# ESP-Breakout_Bd.net
KiCad netlist of a schematic drawn in EAGLE
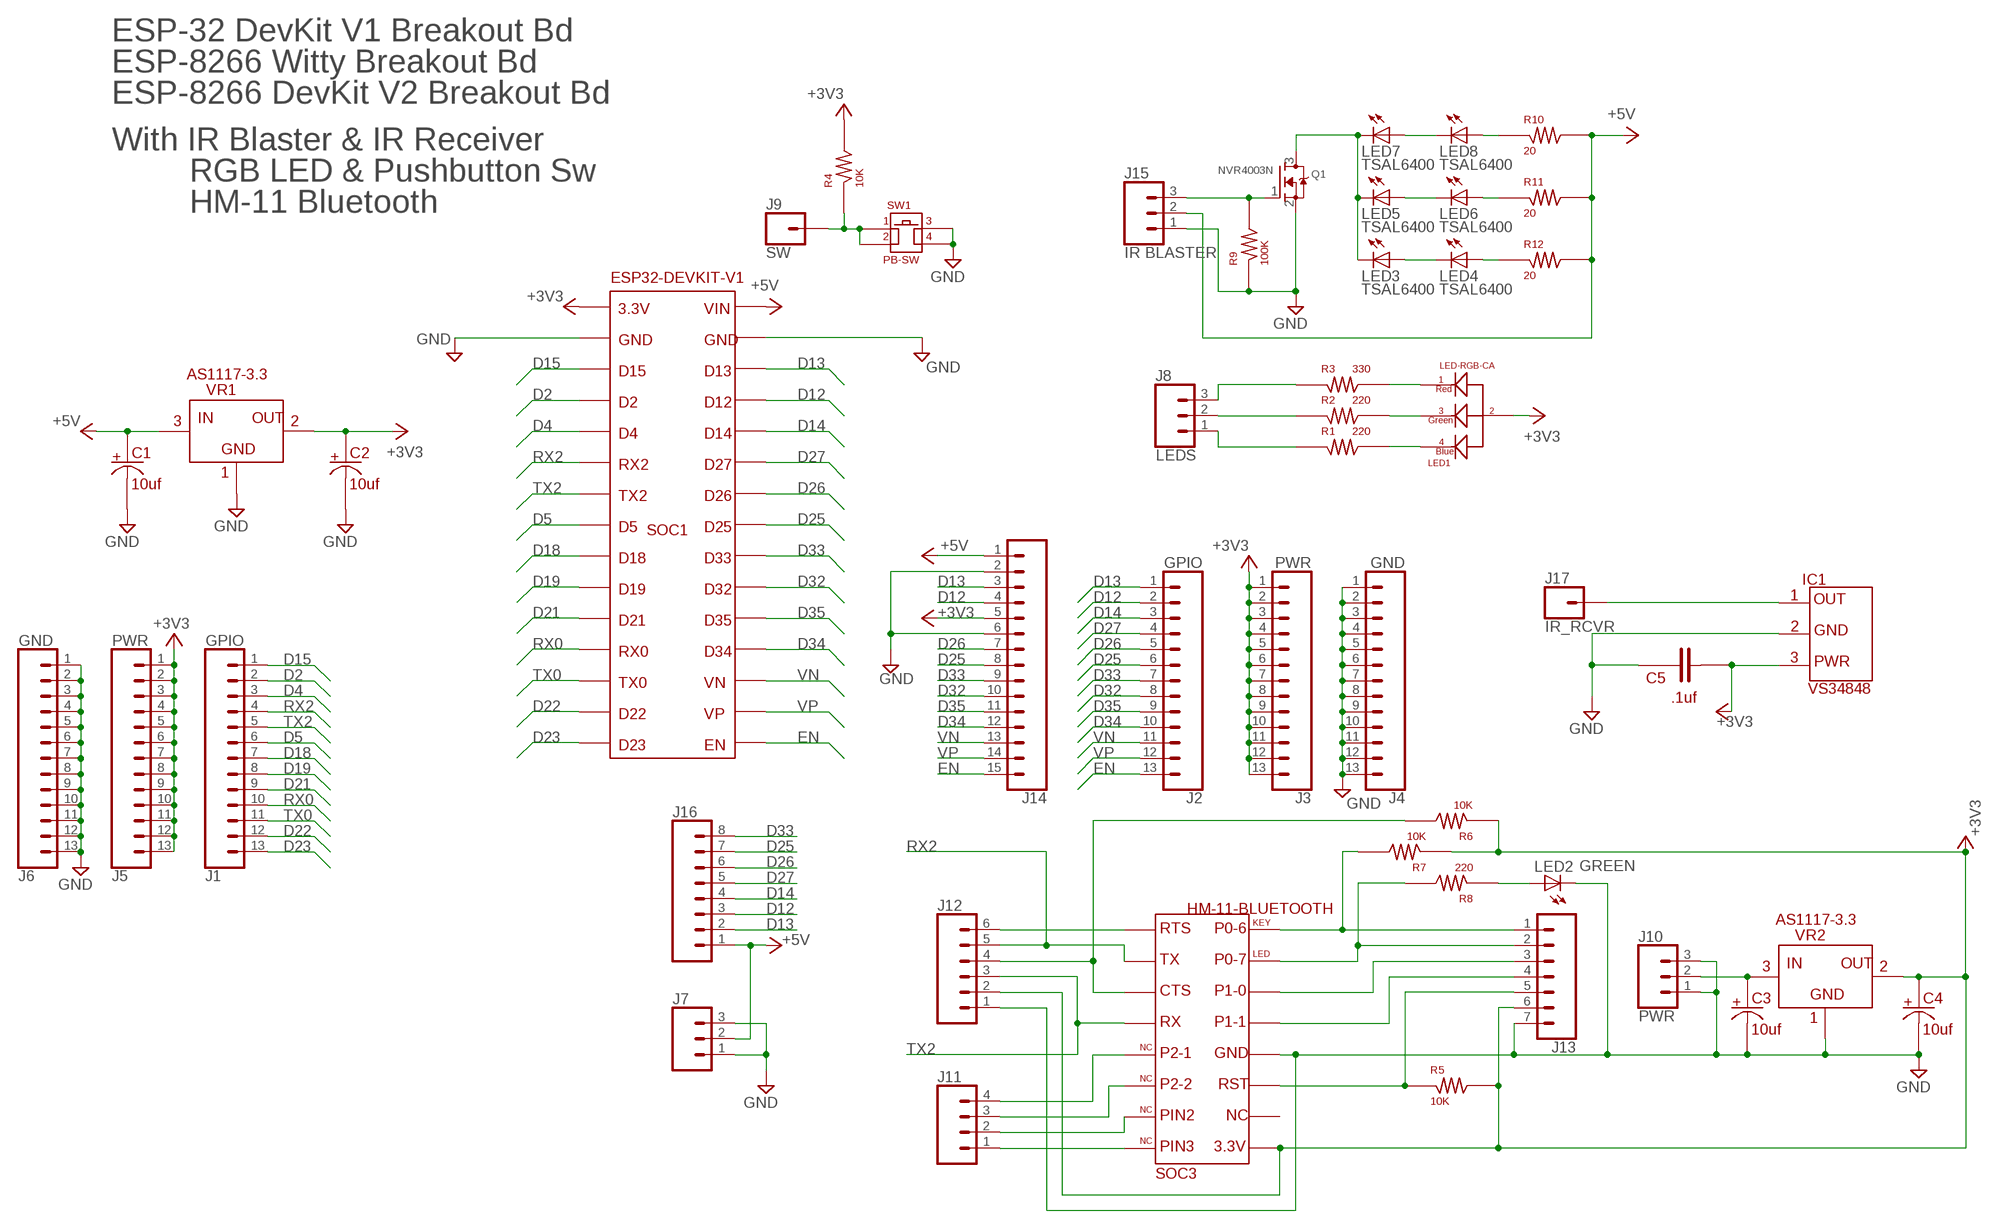
[diagram p0: schematic, sheet 1]

(export (version "E")
  (design (tool "Eeschema 10.0.6"))
  (components
    (comp (ref "C1")
      (value "10uf")
      (footprint "eagle-import:SMT-B")
      (libsource (lib "eagle-import") (part "CAP-POL-SMT-B"))
    )
    (comp (ref "C2")
      (value "10uf")
      (footprint "eagle-import:SMT-B")
      (libsource (lib "eagle-import") (part "CAP-POL-SMT-B"))
    )
    (comp (ref "C3")
      (value "10uf")
      (footprint "eagle-import:SMT-B")
      (libsource (lib "eagle-import") (part "CAP-POL-SMT-B"))
    )
    (comp (ref "C4")
      (value "10uf")
      (footprint "eagle-import:SMT-B")
      (libsource (lib "eagle-import") (part "CAP-POL-SMT-B"))
    )
    (comp (ref "C5")
      (value ".1uf")
      (footprint "eagle-import:CAP-2.5MM-ROUND")
      (libsource (lib "eagle-import") (part "NPCAP-2.5MM-ROUND"))
    )
    (comp (ref "IC1")
      (value "VS34848")
      (footprint "eagle-import:VS34838")
      (libsource (lib "eagle-import") (part "VS34848"))
    )
    (comp (ref "J1")
      (value "GPIO")
      (footprint "eagle-import:1X13")
      (libsource (lib "eagle-import") (part "CONN_13"))
    )
    (comp (ref "J2")
      (value "GPIO")
      (footprint "eagle-import:1X13")
      (libsource (lib "eagle-import") (part "CONN_13"))
    )
    (comp (ref "J3")
      (value "PWR")
      (footprint "eagle-import:1X13")
      (libsource (lib "eagle-import") (part "CONN_13"))
    )
    (comp (ref "J4")
      (value "GND")
      (footprint "eagle-import:1X13")
      (libsource (lib "eagle-import") (part "CONN_13"))
    )
    (comp (ref "J5")
      (value "PWR")
      (footprint "eagle-import:1X13")
      (libsource (lib "eagle-import") (part "CONN_13"))
    )
    (comp (ref "J6")
      (value "GND")
      (footprint "eagle-import:1X13")
      (libsource (lib "eagle-import") (part "CONN_13"))
    )
    (comp (ref "J7")
      (value "CONN_03")
      (footprint "eagle-import:1X03")
      (libsource (lib "eagle-import") (part "CONN_03"))
    )
    (comp (ref "J8")
      (value "LEDS")
      (footprint "eagle-import:1X03")
      (libsource (lib "eagle-import") (part "CONN_03"))
    )
    (comp (ref "J9")
      (value "SW")
      (footprint "eagle-import:1X01")
      (libsource (lib "eagle-import") (part "CONN_01"))
    )
    (comp (ref "J10")
      (value "PWR")
      (footprint "eagle-import:1X03")
      (libsource (lib "eagle-import") (part "CONN_03"))
    )
    (comp (ref "J11")
      (value "CONN_04")
      (footprint "eagle-import:1X04")
      (libsource (lib "eagle-import") (part "CONN_04"))
    )
    (comp (ref "J12")
      (value "CONN_06SILK_FEMALE_PTH")
      (footprint "eagle-import:1X06")
      (libsource (lib "eagle-import") (part "CONN_06SILK_FEMALE_PTH"))
    )
    (comp (ref "J13")
      (value "CONN_07")
      (footprint "eagle-import:1X07")
      (libsource (lib "eagle-import") (part "CONN_07"))
    )
    (comp (ref "J14")
      (value "CONN_15")
      (footprint "eagle-import:1X15")
      (libsource (lib "eagle-import") (part "CONN_15"))
    )
    (comp (ref "J15")
      (value "IR BLASTER")
      (footprint "eagle-import:1X03")
      (libsource (lib "eagle-import") (part "CONN_03"))
    )
    (comp (ref "J16")
      (value "CONN_08\"")
      (footprint "eagle-import:1X08")
      (libsource (lib "eagle-import") (part "CONN_08{dblquote}"))
    )
    (comp (ref "J17")
      (value "IR_RCVR")
      (footprint "eagle-import:1X01")
      (libsource (lib "eagle-import") (part "CONN_01"))
    )
    (comp (ref "LED1")
      (value "LED-RGB-CA")
      (footprint "eagle-import:LED-RGB-5MM")
      (libsource (lib "eagle-import") (part "LED-RGB-CA"))
    )
    (comp (ref "LED2")
      (value "GREEN")
      (footprint "eagle-import:CHIPLED_0805")
      (libsource (lib "eagle-import") (part "LEDCHIPLED_0805"))
    )
    (comp (ref "LED3")
      (value "TSAL6400")
      (footprint "eagle-import:LED5MM")
      (libsource (lib "eagle-import") (part "LED5MM"))
    )
    (comp (ref "LED4")
      (value "TSAL6400")
      (footprint "eagle-import:LED5MM")
      (libsource (lib "eagle-import") (part "LED5MM"))
    )
    (comp (ref "LED5")
      (value "TSAL6400")
      (footprint "eagle-import:LED5MM")
      (libsource (lib "eagle-import") (part "LED5MM"))
    )
    (comp (ref "LED6")
      (value "TSAL6400")
      (footprint "eagle-import:LED5MM")
      (libsource (lib "eagle-import") (part "LED5MM"))
    )
    (comp (ref "LED7")
      (value "TSAL6400")
      (footprint "eagle-import:LED5MM")
      (libsource (lib "eagle-import") (part "LED5MM"))
    )
    (comp (ref "LED8")
      (value "TSAL6400")
      (footprint "eagle-import:LED5MM")
      (libsource (lib "eagle-import") (part "LED5MM"))
    )
    (comp (ref "Q1")
      (value "NVR4003N")
      (footprint "eagle-import:SOT23")
      (libsource (lib "eagle-import") (part "MOSFET-NREFLOW"))
    )
    (comp (ref "R1")
      (value "220")
      (footprint "eagle-import:SMT-1206-TOP")
      (libsource (lib "eagle-import") (part "RESISTOR-1206-TOP"))
    )
    (comp (ref "R2")
      (value "220")
      (footprint "eagle-import:SMT-1206-TOP")
      (libsource (lib "eagle-import") (part "RESISTOR-1206-TOP"))
    )
    (comp (ref "R3")
      (value "330")
      (footprint "eagle-import:SMT-1206-TOP")
      (libsource (lib "eagle-import") (part "RESISTOR-1206-TOP"))
    )
    (comp (ref "R4")
      (value "10K")
      (footprint "eagle-import:SMT-1206-TOP")
      (libsource (lib "eagle-import") (part "RESISTOR-1206-TOP"))
    )
    (comp (ref "R5")
      (value "10K")
      (footprint "eagle-import:SMT-0603")
      (libsource (lib "eagle-import") (part "RESISTOR-SMT-0603"))
    )
    (comp (ref "R6")
      (value "10K")
      (footprint "eagle-import:SMT-0603")
      (libsource (lib "eagle-import") (part "RESISTOR-SMT-0603"))
    )
    (comp (ref "R7")
      (value "10K")
      (footprint "eagle-import:SMT-0603")
      (libsource (lib "eagle-import") (part "RESISTOR-SMT-0603"))
    )
    (comp (ref "R8")
      (value "220")
      (footprint "eagle-import:SMT-0603")
      (libsource (lib "eagle-import") (part "RESISTOR-SMT-0603"))
    )
    (comp (ref "R9")
      (value "100K")
      (footprint "eagle-import:SMT-0603")
      (libsource (lib "eagle-import") (part "RESISTOR-SMT-0603"))
    )
    (comp (ref "R10")
      (value "20")
      (footprint "eagle-import:1_2WATT")
      (libsource (lib "eagle-import") (part "1/2WATT"))
    )
    (comp (ref "R11")
      (value "20")
      (footprint "eagle-import:1_2WATT")
      (libsource (lib "eagle-import") (part "1/2WATT"))
    )
    (comp (ref "R12")
      (value "20")
      (footprint "eagle-import:1_2WATT")
      (libsource (lib "eagle-import") (part "1/2WATT"))
    )
    (comp (ref "SOC1")
      (value "ESP32-DEVKIT-V1")
      (footprint "eagle-import:ESP32-DEVKIT-V1")
      (libsource (lib "eagle-import") (part "ESP32-DEVKIT-V1"))
    )
    (comp (ref "SOC3")
      (value "HM-11-BLUETOOTH")
      (footprint "eagle-import:HM-11")
      (libsource (lib "eagle-import") (part "HM-11-BLUETOOTH"))
    )
    (comp (ref "SW1")
      (value "PB-SW")
      (footprint "eagle-import:PB-SW")
      (libsource (lib "eagle-import") (part "PB-SW"))
    )
    (comp (ref "VR1")
      (value "AS1117-3.3")
      (footprint "eagle-import:SOT-223")
      (libsource (lib "eagle-import") (part "AS1117"))
    )
    (comp (ref "VR2")
      (value "AS1117-3.3")
      (footprint "eagle-import:SOT-223")
      (libsource (lib "eagle-import") (part "AS1117"))
    )
  )
  (nets
    (net (code "1") (name "+3V3") (class "Default")
      (node (ref "C2") (pin "P$1") (pinfunction "P$1_P$1") (pintype "passive"))
      (node (ref "C4") (pin "P$1") (pinfunction "P$1_P$1") (pintype "passive"))
      (node (ref "C5") (pin "P$2") (pinfunction "2_P$2") (pintype "passive"))
      (node (ref "IC1") (pin "P$3") (pinfunction "P$3_P$3") (pintype "bidirectional"))
      (node (ref "J12") (pin "2") (pinfunction "2_2") (pintype "passive"))
      (node (ref "J13") (pin "6") (pinfunction "6_6") (pintype "passive"))
      (node (ref "J14") (pin "5") (pinfunction "5_5") (pintype "passive"))
      (node (ref "J3") (pin "1") (pinfunction "1_1") (pintype "passive"))
      (node (ref "J3") (pin "10") (pinfunction "10_10") (pintype "passive"))
      (node (ref "J3") (pin "11") (pinfunction "11_11") (pintype "passive"))
      (node (ref "J3") (pin "12") (pinfunction "12_12") (pintype "passive"))
      (node (ref "J3") (pin "13") (pinfunction "13_13") (pintype "passive"))
      (node (ref "J3") (pin "2") (pinfunction "2_2") (pintype "passive"))
      (node (ref "J3") (pin "3") (pinfunction "3_3") (pintype "passive"))
      (node (ref "J3") (pin "4") (pinfunction "4_4") (pintype "passive"))
      (node (ref "J3") (pin "5") (pinfunction "5_5") (pintype "passive"))
      (node (ref "J3") (pin "6") (pinfunction "6_6") (pintype "passive"))
      (node (ref "J3") (pin "7") (pinfunction "7_7") (pintype "passive"))
      (node (ref "J3") (pin "8") (pinfunction "8_8") (pintype "passive"))
      (node (ref "J3") (pin "9") (pinfunction "9_9") (pintype "passive"))
      (node (ref "J5") (pin "1") (pinfunction "1_1") (pintype "passive"))
      (node (ref "J5") (pin "10") (pinfunction "10_10") (pintype "passive"))
      (node (ref "J5") (pin "11") (pinfunction "11_11") (pintype "passive"))
      (node (ref "J5") (pin "12") (pinfunction "12_12") (pintype "passive"))
      (node (ref "J5") (pin "13") (pinfunction "13_13") (pintype "passive"))
      (node (ref "J5") (pin "2") (pinfunction "2_2") (pintype "passive"))
      (node (ref "J5") (pin "3") (pinfunction "3_3") (pintype "passive"))
      (node (ref "J5") (pin "4") (pinfunction "4_4") (pintype "passive"))
      (node (ref "J5") (pin "5") (pinfunction "5_5") (pintype "passive"))
      (node (ref "J5") (pin "6") (pinfunction "6_6") (pintype "passive"))
      (node (ref "J5") (pin "7") (pinfunction "7_7") (pintype "passive"))
      (node (ref "J5") (pin "8") (pinfunction "8_8") (pintype "passive"))
      (node (ref "J5") (pin "9") (pinfunction "9_9") (pintype "passive"))
      (node (ref "LED1") (pin "P$2") (pinfunction "P$2_P$2") (pintype "bidirectional"))
      (node (ref "R4") (pin "P$2") (pinfunction "P$2_P$2") (pintype "bidirectional"))
      (node (ref "R5") (pin "P$2") (pinfunction "P$2_P$2") (pintype "bidirectional"))
      (node (ref "R6") (pin "P$1") (pinfunction "P$1_P$1") (pintype "bidirectional"))
      (node (ref "R7") (pin "P$1") (pinfunction "P$1_P$1") (pintype "bidirectional"))
      (node (ref "SOC1") (pin "P$1") (pinfunction "P$1_P$1") (pintype "bidirectional"))
      (node (ref "SOC3") (pin "P$9") (pinfunction "P$9_P$9") (pintype "bidirectional"))
      (node (ref "VR1") (pin "P$2") (pinfunction "P$2_P$2") (pintype "bidirectional"))
      (node (ref "VR1") (pin "P$4") (pinfunction "P$2_P$4") (pintype "bidirectional"))
      (node (ref "VR2") (pin "P$2") (pinfunction "P$2_P$2") (pintype "bidirectional"))
      (node (ref "VR2") (pin "P$4") (pinfunction "P$2_P$4") (pintype "bidirectional"))
    )
    (net (code "2") (name "+5V") (class "Default")
      (node (ref "C1") (pin "P$1") (pinfunction "P$1_P$1") (pintype "passive"))
      (node (ref "J14") (pin "1") (pinfunction "1_1") (pintype "passive"))
      (node (ref "J15") (pin "2") (pinfunction "2_2") (pintype "passive"))
      (node (ref "J16") (pin "1") (pinfunction "1_1") (pintype "passive"))
      (node (ref "J7") (pin "2") (pinfunction "2_2") (pintype "passive"))
      (node (ref "R10") (pin "P$2") (pinfunction "P$2_P$2") (pintype "bidirectional"))
      (node (ref "R11") (pin "P$2") (pinfunction "P$2_P$2") (pintype "bidirectional"))
      (node (ref "R12") (pin "P$2") (pinfunction "P$2_P$2") (pintype "bidirectional"))
      (node (ref "SOC1") (pin "P$30") (pinfunction "P$30_P$30") (pintype "bidirectional"))
      (node (ref "VR1") (pin "P$3") (pinfunction "P$3_P$3") (pintype "bidirectional"))
    )
    (net (code "3") (name "/D2") (class "Default")
      (node (ref "J1") (pin "2") (pinfunction "2_2") (pintype "passive"))
      (node (ref "SOC1") (pin "P$4") (pinfunction "P$4_P$4") (pintype "bidirectional"))
    )
    (net (code "4") (name "/D4") (class "Default")
      (node (ref "J1") (pin "3") (pinfunction "3_3") (pintype "passive"))
      (node (ref "SOC1") (pin "P$5") (pinfunction "P$5_P$5") (pintype "bidirectional"))
    )
    (net (code "5") (name "/D5") (class "Default")
      (node (ref "J1") (pin "6") (pinfunction "6_6") (pintype "passive"))
      (node (ref "SOC1") (pin "P$8") (pinfunction "P$8_P$8") (pintype "bidirectional"))
    )
    (net (code "6") (name "/D12") (class "Default")
      (node (ref "J14") (pin "4") (pinfunction "4_4") (pintype "passive"))
      (node (ref "J16") (pin "3") (pinfunction "3_3") (pintype "passive"))
      (node (ref "J2") (pin "2") (pinfunction "2_2") (pintype "passive"))
      (node (ref "SOC1") (pin "P$27") (pinfunction "P$27_P$27") (pintype "bidirectional"))
    )
    (net (code "7") (name "/D13") (class "Default")
      (node (ref "J14") (pin "3") (pinfunction "3_3") (pintype "passive"))
      (node (ref "J16") (pin "2") (pinfunction "2_2") (pintype "passive"))
      (node (ref "J2") (pin "1") (pinfunction "1_1") (pintype "passive"))
      (node (ref "SOC1") (pin "P$28") (pinfunction "P$28_P$28") (pintype "bidirectional"))
    )
    (net (code "8") (name "/D14") (class "Default")
      (node (ref "J16") (pin "4") (pinfunction "4_4") (pintype "passive"))
      (node (ref "J2") (pin "3") (pinfunction "3_3") (pintype "passive"))
      (node (ref "SOC1") (pin "P$26") (pinfunction "P$26_P$26") (pintype "bidirectional"))
    )
    (net (code "9") (name "/D15") (class "Default")
      (node (ref "J1") (pin "1") (pinfunction "1_1") (pintype "passive"))
      (node (ref "SOC1") (pin "P$3") (pinfunction "P$3_P$3") (pintype "bidirectional"))
    )
    (net (code "10") (name "/D18") (class "Default")
      (node (ref "J1") (pin "7") (pinfunction "7_7") (pintype "passive"))
      (node (ref "SOC1") (pin "P$9") (pinfunction "P$9_P$9") (pintype "bidirectional"))
    )
    (net (code "11") (name "/D19") (class "Default")
      (node (ref "J1") (pin "8") (pinfunction "8_8") (pintype "passive"))
      (node (ref "SOC1") (pin "P$10") (pinfunction "P$10_P$10") (pintype "bidirectional"))
    )
    (net (code "12") (name "/D21") (class "Default")
      (node (ref "J1") (pin "9") (pinfunction "9_9") (pintype "passive"))
      (node (ref "SOC1") (pin "P$11") (pinfunction "P$11_P$11") (pintype "bidirectional"))
    )
    (net (code "13") (name "/D22") (class "Default")
      (node (ref "J1") (pin "12") (pinfunction "12_12") (pintype "passive"))
      (node (ref "SOC1") (pin "P$14") (pinfunction "P$14_P$14") (pintype "bidirectional"))
    )
    (net (code "14") (name "/D23") (class "Default")
      (node (ref "J1") (pin "13") (pinfunction "13_13") (pintype "passive"))
      (node (ref "SOC1") (pin "P$15") (pinfunction "P$15_P$15") (pintype "bidirectional"))
    )
    (net (code "15") (name "/D25") (class "Default")
      (node (ref "J14") (pin "8") (pinfunction "8_8") (pintype "passive"))
      (node (ref "J16") (pin "7") (pinfunction "7_7") (pintype "passive"))
      (node (ref "J2") (pin "6") (pinfunction "6_6") (pintype "passive"))
      (node (ref "SOC1") (pin "P$23") (pinfunction "P$23_P$23") (pintype "bidirectional"))
    )
    (net (code "16") (name "/D26") (class "Default")
      (node (ref "J14") (pin "7") (pinfunction "7_7") (pintype "passive"))
      (node (ref "J16") (pin "6") (pinfunction "6_6") (pintype "passive"))
      (node (ref "J2") (pin "5") (pinfunction "5_5") (pintype "passive"))
      (node (ref "SOC1") (pin "P$24") (pinfunction "P$24_P$24") (pintype "bidirectional"))
    )
    (net (code "17") (name "/D27") (class "Default")
      (node (ref "J16") (pin "5") (pinfunction "5_5") (pintype "passive"))
      (node (ref "J2") (pin "4") (pinfunction "4_4") (pintype "passive"))
      (node (ref "SOC1") (pin "P$25") (pinfunction "P$25_P$25") (pintype "bidirectional"))
    )
    (net (code "18") (name "/D32") (class "Default")
      (node (ref "J14") (pin "10") (pinfunction "10_10") (pintype "passive"))
      (node (ref "J2") (pin "8") (pinfunction "8_8") (pintype "passive"))
      (node (ref "SOC1") (pin "P$21") (pinfunction "P$21_P$21") (pintype "bidirectional"))
    )
    (net (code "19") (name "/D33") (class "Default")
      (node (ref "J14") (pin "9") (pinfunction "9_9") (pintype "passive"))
      (node (ref "J16") (pin "8") (pinfunction "8_8") (pintype "passive"))
      (node (ref "J2") (pin "7") (pinfunction "7_7") (pintype "passive"))
      (node (ref "SOC1") (pin "P$22") (pinfunction "P$22_P$22") (pintype "bidirectional"))
    )
    (net (code "20") (name "/D34") (class "Default")
      (node (ref "J14") (pin "12") (pinfunction "12_12") (pintype "passive"))
      (node (ref "J2") (pin "10") (pinfunction "10_10") (pintype "passive"))
      (node (ref "SOC1") (pin "P$19") (pinfunction "P$19_P$19") (pintype "bidirectional"))
    )
    (net (code "21") (name "/D35") (class "Default")
      (node (ref "J14") (pin "11") (pinfunction "11_11") (pintype "passive"))
      (node (ref "J2") (pin "9") (pinfunction "9_9") (pintype "passive"))
      (node (ref "SOC1") (pin "P$20") (pinfunction "P$20_P$20") (pintype "bidirectional"))
    )
    (net (code "22") (name "/EN") (class "Default")
      (node (ref "J14") (pin "15") (pinfunction "15_15") (pintype "passive"))
      (node (ref "J2") (pin "13") (pinfunction "13_13") (pintype "passive"))
      (node (ref "SOC1") (pin "P$16") (pinfunction "P$16_P$16") (pintype "bidirectional"))
    )
    (net (code "23") (name "/RX0") (class "Default")
      (node (ref "J1") (pin "10") (pinfunction "10_10") (pintype "passive"))
      (node (ref "SOC1") (pin "P$12") (pinfunction "P$12_P$12") (pintype "bidirectional"))
    )
    (net (code "24") (name "/RX2") (class "Default")
      (node (ref "J1") (pin "4") (pinfunction "4_4") (pintype "passive"))
      (node (ref "J12") (pin "5") (pinfunction "5_5") (pintype "passive"))
      (node (ref "SOC1") (pin "P$6") (pinfunction "P$6_P$6") (pintype "bidirectional"))
      (node (ref "SOC3") (pin "P$2") (pinfunction "P$2_P$2") (pintype "bidirectional"))
    )
    (net (code "25") (name "/TX0") (class "Default")
      (node (ref "J1") (pin "11") (pinfunction "11_11") (pintype "passive"))
      (node (ref "SOC1") (pin "P$13") (pinfunction "P$13_P$13") (pintype "bidirectional"))
    )
    (net (code "26") (name "/TX2") (class "Default")
      (node (ref "J1") (pin "5") (pinfunction "5_5") (pintype "passive"))
      (node (ref "J12") (pin "3") (pinfunction "3_3") (pintype "passive"))
      (node (ref "SOC1") (pin "P$7") (pinfunction "P$7_P$7") (pintype "bidirectional"))
      (node (ref "SOC3") (pin "P$4") (pinfunction "P$4_P$4") (pintype "bidirectional"))
    )
    (net (code "27") (name "/VN") (class "Default")
      (node (ref "J14") (pin "13") (pinfunction "13_13") (pintype "passive"))
      (node (ref "J2") (pin "11") (pinfunction "11_11") (pintype "passive"))
      (node (ref "SOC1") (pin "P$18") (pinfunction "P$18_P$18") (pintype "bidirectional"))
    )
    (net (code "28") (name "/VP") (class "Default")
      (node (ref "J14") (pin "14") (pinfunction "14_14") (pintype "passive"))
      (node (ref "J2") (pin "12") (pinfunction "12_12") (pintype "passive"))
      (node (ref "SOC1") (pin "P$17") (pinfunction "P$17_P$17") (pintype "bidirectional"))
    )
    (net (code "29") (name "GND") (class "Default")
      (node (ref "C1") (pin "P$2") (pinfunction "P$2_P$2") (pintype "passive"))
      (node (ref "C2") (pin "P$2") (pinfunction "P$2_P$2") (pintype "passive"))
      (node (ref "C3") (pin "P$2") (pinfunction "P$2_P$2") (pintype "passive"))
      (node (ref "C4") (pin "P$2") (pinfunction "P$2_P$2") (pintype "passive"))
      (node (ref "C5") (pin "P$1") (pinfunction "1_P$1") (pintype "passive"))
      (node (ref "IC1") (pin "P$2") (pinfunction "P$2_P$2") (pintype "bidirectional"))
      (node (ref "J10") (pin "1") (pinfunction "1_1") (pintype "passive"))
      (node (ref "J10") (pin "3") (pinfunction "3_3") (pintype "passive"))
      (node (ref "J12") (pin "1") (pinfunction "1_1") (pintype "passive"))
      (node (ref "J13") (pin "7") (pinfunction "7_7") (pintype "passive"))
      (node (ref "J14") (pin "2") (pinfunction "2_2") (pintype "passive"))
      (node (ref "J14") (pin "6") (pinfunction "6_6") (pintype "passive"))
      (node (ref "J15") (pin "1") (pinfunction "1_1") (pintype "passive"))
      (node (ref "J4") (pin "1") (pinfunction "1_1") (pintype "passive"))
      (node (ref "J4") (pin "10") (pinfunction "10_10") (pintype "passive"))
      (node (ref "J4") (pin "11") (pinfunction "11_11") (pintype "passive"))
      (node (ref "J4") (pin "12") (pinfunction "12_12") (pintype "passive"))
      (node (ref "J4") (pin "13") (pinfunction "13_13") (pintype "passive"))
      (node (ref "J4") (pin "2") (pinfunction "2_2") (pintype "passive"))
      (node (ref "J4") (pin "3") (pinfunction "3_3") (pintype "passive"))
      (node (ref "J4") (pin "4") (pinfunction "4_4") (pintype "passive"))
      (node (ref "J4") (pin "5") (pinfunction "5_5") (pintype "passive"))
      (node (ref "J4") (pin "6") (pinfunction "6_6") (pintype "passive"))
      (node (ref "J4") (pin "7") (pinfunction "7_7") (pintype "passive"))
      (node (ref "J4") (pin "8") (pinfunction "8_8") (pintype "passive"))
      (node (ref "J4") (pin "9") (pinfunction "9_9") (pintype "passive"))
      (node (ref "J6") (pin "1") (pinfunction "1_1") (pintype "passive"))
      (node (ref "J6") (pin "10") (pinfunction "10_10") (pintype "passive"))
      (node (ref "J6") (pin "11") (pinfunction "11_11") (pintype "passive"))
      (node (ref "J6") (pin "12") (pinfunction "12_12") (pintype "passive"))
      (node (ref "J6") (pin "13") (pinfunction "13_13") (pintype "passive"))
      (node (ref "J6") (pin "2") (pinfunction "2_2") (pintype "passive"))
      (node (ref "J6") (pin "3") (pinfunction "3_3") (pintype "passive"))
      (node (ref "J6") (pin "4") (pinfunction "4_4") (pintype "passive"))
      (node (ref "J6") (pin "5") (pinfunction "5_5") (pintype "passive"))
      (node (ref "J6") (pin "6") (pinfunction "6_6") (pintype "passive"))
      (node (ref "J6") (pin "7") (pinfunction "7_7") (pintype "passive"))
      (node (ref "J6") (pin "8") (pinfunction "8_8") (pintype "passive"))
      (node (ref "J6") (pin "9") (pinfunction "9_9") (pintype "passive"))
      (node (ref "J7") (pin "1") (pinfunction "1_1") (pintype "passive"))
      (node (ref "J7") (pin "3") (pinfunction "3_3") (pintype "passive"))
      (node (ref "LED2") (pin "C") (pinfunction "C_C") (pintype "passive"))
      (node (ref "Q1") (pin "2") (pinfunction "S_2") (pintype "bidirectional"))
      (node (ref "R9") (pin "P$1") (pinfunction "P$1_P$1") (pintype "bidirectional"))
      (node (ref "SOC1") (pin "P$2") (pinfunction "P$2_P$2") (pintype "bidirectional"))
      (node (ref "SOC1") (pin "P$29") (pinfunction "P$29_P$29") (pintype "bidirectional"))
      (node (ref "SOC3") (pin "P$12") (pinfunction "P$12_P$12") (pintype "bidirectional"))
      (node (ref "SW1") (pin "P$3") (pinfunction "P$3_P$3") (pintype "bidirectional"))
      (node (ref "SW1") (pin "P$4") (pinfunction "P$4_P$4") (pintype "bidirectional"))
      (node (ref "VR1") (pin "P$1") (pinfunction "P$1_P$1") (pintype "bidirectional"))
      (node (ref "VR2") (pin "P$1") (pinfunction "P$1_P$1") (pintype "bidirectional"))
    )
    (net (code "30") (name "Net-(C3-PadP$1)") (class "Default")
      (node (ref "C3") (pin "P$1") (pinfunction "P$1_P$1") (pintype "passive"))
      (node (ref "J10") (pin "2") (pinfunction "2_2") (pintype "passive"))
      (node (ref "VR2") (pin "P$3") (pinfunction "P$3_P$3") (pintype "bidirectional"))
    )
    (net (code "31") (name "Net-(IC1-PadP$1)") (class "Default")
      (node (ref "IC1") (pin "P$1") (pinfunction "P$1_P$1") (pintype "bidirectional"))
      (node (ref "J17") (pin "1") (pinfunction "1_1") (pintype "passive"))
    )
    (net (code "32") (name "Net-(J8-Pad1)") (class "Default")
      (node (ref "J8") (pin "1") (pinfunction "1_1") (pintype "passive"))
      (node (ref "R1") (pin "P$1") (pinfunction "P$1_P$1") (pintype "bidirectional"))
    )
    (net (code "33") (name "Net-(J8-Pad2)") (class "Default")
      (node (ref "J8") (pin "2") (pinfunction "2_2") (pintype "passive"))
      (node (ref "R2") (pin "P$1") (pinfunction "P$1_P$1") (pintype "bidirectional"))
    )
    (net (code "34") (name "Net-(J8-Pad3)") (class "Default")
      (node (ref "J8") (pin "3") (pinfunction "3_3") (pintype "passive"))
      (node (ref "R3") (pin "P$1") (pinfunction "P$1_P$1") (pintype "bidirectional"))
    )
    (net (code "35") (name "Net-(J9-Pad1)") (class "Default")
      (node (ref "J9") (pin "1") (pinfunction "1_1") (pintype "passive"))
      (node (ref "R4") (pin "P$1") (pinfunction "P$1_P$1") (pintype "bidirectional"))
      (node (ref "SW1") (pin "P$1") (pinfunction "P$1_P$1") (pintype "bidirectional"))
      (node (ref "SW1") (pin "P$2") (pinfunction "P$2_P$2") (pintype "bidirectional"))
    )
    (net (code "36") (name "Net-(J11-Pad1)") (class "Default")
      (node (ref "J11") (pin "1") (pinfunction "1_1") (pintype "passive"))
      (node (ref "SOC3") (pin "P$8") (pinfunction "P$8_P$8") (pintype "bidirectional"))
    )
    (net (code "37") (name "Net-(J11-Pad2)") (class "Default")
      (node (ref "J11") (pin "2") (pinfunction "2_2") (pintype "passive"))
      (node (ref "SOC3") (pin "P$7") (pinfunction "P$7_P$7") (pintype "bidirectional"))
    )
    (net (code "38") (name "Net-(J11-Pad3)") (class "Default")
      (node (ref "J11") (pin "3") (pinfunction "3_3") (pintype "passive"))
      (node (ref "SOC3") (pin "P$6") (pinfunction "P$6_P$6") (pintype "bidirectional"))
    )
    (net (code "39") (name "Net-(J11-Pad4)") (class "Default")
      (node (ref "J11") (pin "4") (pinfunction "4_4") (pintype "passive"))
      (node (ref "SOC3") (pin "P$5") (pinfunction "P$5_P$5") (pintype "bidirectional"))
    )
    (net (code "40") (name "Net-(J12-Pad4)") (class "Default")
      (node (ref "J12") (pin "4") (pinfunction "4_4") (pintype "passive"))
      (node (ref "R6") (pin "P$2") (pinfunction "P$2_P$2") (pintype "bidirectional"))
      (node (ref "SOC3") (pin "P$3") (pinfunction "P$3_P$3") (pintype "bidirectional"))
    )
    (net (code "41") (name "Net-(J12-Pad6)") (class "Default")
      (node (ref "J12") (pin "6") (pinfunction "6_6") (pintype "passive"))
      (node (ref "SOC3") (pin "P$1") (pinfunction "P$1_P$1") (pintype "bidirectional"))
    )
    (net (code "42") (name "Net-(J13-Pad1)") (class "Default")
      (node (ref "J13") (pin "1") (pinfunction "1_1") (pintype "passive"))
      (node (ref "R7") (pin "P$2") (pinfunction "P$2_P$2") (pintype "bidirectional"))
      (node (ref "SOC3") (pin "P$16") (pinfunction "P$16_P$16") (pintype "bidirectional"))
    )
    (net (code "43") (name "Net-(J13-Pad2)") (class "Default")
      (node (ref "J13") (pin "2") (pinfunction "2_2") (pintype "passive"))
      (node (ref "R8") (pin "P$2") (pinfunction "P$2_P$2") (pintype "bidirectional"))
      (node (ref "SOC3") (pin "P$15") (pinfunction "P$15_P$15") (pintype "bidirectional"))
    )
    (net (code "44") (name "Net-(J13-Pad3)") (class "Default")
      (node (ref "J13") (pin "3") (pinfunction "3_3") (pintype "passive"))
      (node (ref "SOC3") (pin "P$14") (pinfunction "P$14_P$14") (pintype "bidirectional"))
    )
    (net (code "45") (name "Net-(J13-Pad4)") (class "Default")
      (node (ref "J13") (pin "4") (pinfunction "4_4") (pintype "passive"))
      (node (ref "SOC3") (pin "P$13") (pinfunction "P$13_P$13") (pintype "bidirectional"))
    )
    (net (code "46") (name "Net-(J13-Pad5)") (class "Default")
      (node (ref "J13") (pin "5") (pinfunction "5_5") (pintype "passive"))
      (node (ref "R5") (pin "P$1") (pinfunction "P$1_P$1") (pintype "bidirectional"))
      (node (ref "SOC3") (pin "P$11") (pinfunction "P$11_P$11") (pintype "bidirectional"))
    )
    (net (code "47") (name "Net-(LED1-PadP$1)") (class "Default")
      (node (ref "LED1") (pin "P$1") (pinfunction "P$1_P$1") (pintype "bidirectional"))
      (node (ref "R3") (pin "P$2") (pinfunction "P$2_P$2") (pintype "bidirectional"))
    )
    (net (code "48") (name "Net-(LED1-PadP$3)") (class "Default")
      (node (ref "LED1") (pin "P$3") (pinfunction "P$3_P$3") (pintype "bidirectional"))
      (node (ref "R2") (pin "P$2") (pinfunction "P$2_P$2") (pintype "bidirectional"))
    )
    (net (code "49") (name "Net-(LED1-PadP$4)") (class "Default")
      (node (ref "LED1") (pin "P$4") (pinfunction "P$4_P$4") (pintype "bidirectional"))
      (node (ref "R1") (pin "P$2") (pinfunction "P$2_P$2") (pintype "bidirectional"))
    )
    (net (code "50") (name "Net-(LED2-PadA)") (class "Default")
      (node (ref "LED2") (pin "A") (pinfunction "A_A") (pintype "passive"))
      (node (ref "R8") (pin "P$1") (pinfunction "P$1_P$1") (pintype "bidirectional"))
    )
    (net (code "51") (name "Net-(LED3-C)") (class "Default")
      (node (ref "LED3") (pin "K") (pinfunction "C_K") (pintype "passive"))
      (node (ref "LED5") (pin "K") (pinfunction "C_K") (pintype "passive"))
      (node (ref "LED7") (pin "K") (pinfunction "C_K") (pintype "passive"))
      (node (ref "Q1") (pin "3") (pinfunction "D_3") (pintype "bidirectional"))
    )
    (net (code "52") (name "Net-(LED4-C)") (class "Default")
      (node (ref "LED3") (pin "A") (pinfunction "A_A") (pintype "passive"))
      (node (ref "LED4") (pin "K") (pinfunction "C_K") (pintype "passive"))
    )
    (net (code "53") (name "Net-(LED4-PadA)") (class "Default")
      (node (ref "LED4") (pin "A") (pinfunction "A_A") (pintype "passive"))
      (node (ref "R12") (pin "P$1") (pinfunction "P$1_P$1") (pintype "bidirectional"))
    )
    (net (code "54") (name "Net-(LED6-C)") (class "Default")
      (node (ref "LED5") (pin "A") (pinfunction "A_A") (pintype "passive"))
      (node (ref "LED6") (pin "K") (pinfunction "C_K") (pintype "passive"))
    )
    (net (code "55") (name "Net-(LED6-PadA)") (class "Default")
      (node (ref "LED6") (pin "A") (pinfunction "A_A") (pintype "passive"))
      (node (ref "R11") (pin "P$1") (pinfunction "P$1_P$1") (pintype "bidirectional"))
    )
    (net (code "56") (name "Net-(LED8-C)") (class "Default")
      (node (ref "LED7") (pin "A") (pinfunction "A_A") (pintype "passive"))
      (node (ref "LED8") (pin "K") (pinfunction "C_K") (pintype "passive"))
    )
    (net (code "57") (name "Net-(LED8-PadA)") (class "Default")
      (node (ref "LED8") (pin "A") (pinfunction "A_A") (pintype "passive"))
      (node (ref "R10") (pin "P$1") (pinfunction "P$1_P$1") (pintype "bidirectional"))
    )
    (net (code "58") (name "Net-(Q1-G)") (class "Default")
      (node (ref "J15") (pin "3") (pinfunction "3_3") (pintype "passive"))
      (node (ref "Q1") (pin "1") (pinfunction "G_1") (pintype "bidirectional"))
      (node (ref "R9") (pin "P$2") (pinfunction "P$2_P$2") (pintype "bidirectional"))
    )
    (net (code "59") (name "unconnected-(SOC3-PadP$10)") (class "Default")
      (node (ref "SOC3") (pin "P$10") (pinfunction "P$10_P$10") (pintype "bidirectional"))
    )
  )
)
